# Sheet-3.net
KiCad netlist of a schematic drawn in Altium Designer
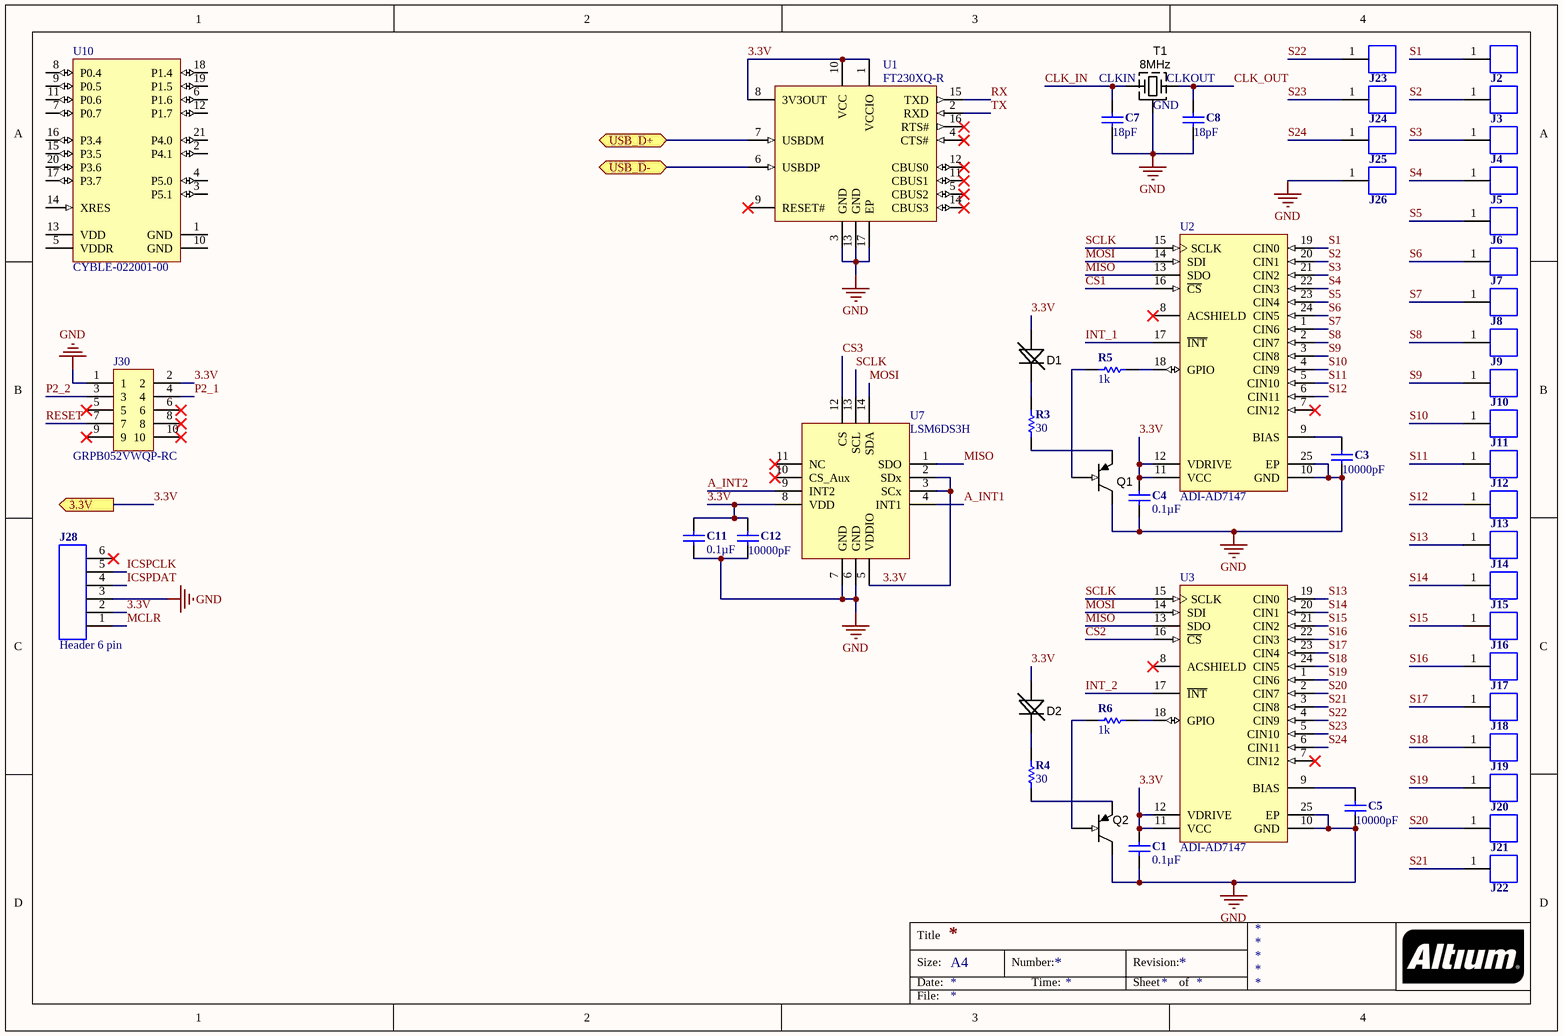
[diagram p0: Sheet-3.SchDoc]

(export (version "E")
  (design (tool "Eeschema 10.0.6"))
  (components
    (comp (ref "C1")
      (value "0.1µF")
      (footprint "CAP-0805(2012)-R")
      (description "___ OHM ___ mW 0805(2012) SMD")
      (fields
        (field (name "MANUFACTURER") "Yageo")
        (field (name "MANUFACTURER PART NUMBER") "CC0805KRX7R9BB104")
      )
      (libsource (lib "Glove") (part "C-0805(2012)"))
    )
    (comp (ref "C3")
      (value "10000pF")
      (footprint "CAP-0805(2012)-R")
      (description "___ OHM ___ mW 0805(2012) SMD")
      (fields
        (field (name "MANUFACTURER") "Yageo")
        (field (name "MANUFACTURER PART NUMBER") "CC0805KRX7R9BB103")
      )
      (libsource (lib "Glove") (part "C-0805(2012)"))
    )
    (comp (ref "C4")
      (value "0.1µF")
      (footprint "CAP-0805(2012)-R")
      (description "___ OHM ___ mW 0805(2012) SMD")
      (fields
        (field (name "MANUFACTURER") "Yageo")
        (field (name "MANUFACTURER PART NUMBER") "CC0805KRX7R9BB104")
      )
      (libsource (lib "Glove") (part "C-0805(2012)"))
    )
    (comp (ref "C5")
      (value "10000pF")
      (footprint "CAP-0805(2012)-R")
      (description "___ OHM ___ mW 0805(2012) SMD")
      (fields
        (field (name "MANUFACTURER") "Yageo")
        (field (name "MANUFACTURER PART NUMBER") "CC0805KRX7R9BB103")
      )
      (libsource (lib "Glove") (part "C-0805(2012)"))
    )
    (comp (ref "C7")
      (value "18pF")
      (footprint "CAP-0805(2012)-R")
      (description "___ OHM ___ mW 0805(2012) SMD")
      (fields
        (field (name "MANUFACTURER") "Yageo")
        (field (name "MANUFACTURER PART NUMBER") "CC0805JRNPO9BN180")
      )
      (libsource (lib "Glove") (part "C-0805(2012)"))
    )
    (comp (ref "C8")
      (value "18pF")
      (footprint "CAP-0805(2012)-R")
      (description "___ OHM ___ mW 0805(2012) SMD")
      (fields
        (field (name "MANUFACTURER") "Yageo")
        (field (name "MANUFACTURER PART NUMBER") "CC0805JRNPO9BN180")
      )
      (libsource (lib "Glove") (part "C-0805(2012)"))
    )
    (comp (ref "C11")
      (value "0.1µF")
      (footprint "CAP-0805(2012)-R")
      (description "___ OHM ___ mW 0805(2012) SMD")
      (fields
        (field (name "MANUFACTURER") "Yageo")
        (field (name "MANUFACTURER PART NUMBER") "CC0805KRX7R9BB104")
      )
      (libsource (lib "Glove") (part "C-0805(2012)"))
    )
    (comp (ref "C12")
      (value "10000pF")
      (footprint "CAP-0805(2012)-R")
      (description "___ OHM ___ mW 0805(2012) SMD")
      (fields
        (field (name "MANUFACTURER") "Yageo")
        (field (name "MANUFACTURER PART NUMBER") "CC0805KRX7R9BB103")
      )
      (libsource (lib "Glove") (part "C-0805(2012)"))
    )
    (comp (ref "D1")
      (value "YELLOW")
      (footprint "LED-0805-A")
      (description "LED, 0805 SMD, YELLOW")
      (fields
        (field (name "MANUFACTURER") "OSRAM Opto Semiconductors Inc.")
        (field (name "MANUFACTURER PART NUMBER") "LY R976-PS-36")
      )
      (libsource (lib "Glove") (part "LED_0805_YELLOW"))
    )
    (comp (ref "D2")
      (value "YELLOW")
      (footprint "LED-0805-A")
      (description "LED, 0805 SMD, YELLOW")
      (fields
        (field (name "MANUFACTURER") "OSRAM Opto Semiconductors Inc.")
        (field (name "MANUFACTURER PART NUMBER") "LY R976-PS-36")
      )
      (libsource (lib "Glove") (part "LED_0805_YELLOW"))
    )
    (comp (ref "J2")
      (value "Conductive Thread")
      (footprint "THREAD_HOLE")
      (description "Header, 1 pin, Conductive Thread")
      (libsource (lib "Glove") (part "CON-1_Pin_Thread"))
    )
    (comp (ref "J3")
      (value "Conductive Thread")
      (footprint "THREAD_HOLE")
      (description "Header, 1 pin, Conductive Thread")
      (libsource (lib "Glove") (part "CON-1_Pin_Thread"))
    )
    (comp (ref "J4")
      (value "Conductive Thread")
      (footprint "THREAD_HOLE")
      (description "Header, 1 pin, Conductive Thread")
      (libsource (lib "Glove") (part "CON-1_Pin_Thread"))
    )
    (comp (ref "J5")
      (value "Conductive Thread")
      (footprint "THREAD_HOLE")
      (description "Header, 1 pin, Conductive Thread")
      (libsource (lib "Glove") (part "CON-1_Pin_Thread"))
    )
    (comp (ref "J6")
      (value "Conductive Thread")
      (footprint "THREAD_HOLE")
      (description "Header, 1 pin, Conductive Thread")
      (libsource (lib "Glove") (part "CON-1_Pin_Thread"))
    )
    (comp (ref "J7")
      (value "Conductive Thread")
      (footprint "THREAD_HOLE")
      (description "Header, 1 pin, Conductive Thread")
      (libsource (lib "Glove") (part "CON-1_Pin_Thread"))
    )
    (comp (ref "J8")
      (value "Conductive Thread")
      (footprint "THREAD_HOLE")
      (description "Header, 1 pin, Conductive Thread")
      (libsource (lib "Glove") (part "CON-1_Pin_Thread"))
    )
    (comp (ref "J9")
      (value "Conductive Thread")
      (footprint "THREAD_HOLE")
      (description "Header, 1 pin, Conductive Thread")
      (libsource (lib "Glove") (part "CON-1_Pin_Thread"))
    )
    (comp (ref "J10")
      (value "Conductive Thread")
      (footprint "THREAD_HOLE")
      (description "Header, 1 pin, Conductive Thread")
      (libsource (lib "Glove") (part "CON-1_Pin_Thread"))
    )
    (comp (ref "J11")
      (value "Conductive Thread")
      (footprint "THREAD_HOLE")
      (description "Header, 1 pin, Conductive Thread")
      (libsource (lib "Glove") (part "CON-1_Pin_Thread"))
    )
    (comp (ref "J12")
      (value "Conductive Thread")
      (footprint "THREAD_HOLE")
      (description "Header, 1 pin, Conductive Thread")
      (libsource (lib "Glove") (part "CON-1_Pin_Thread"))
    )
    (comp (ref "J13")
      (value "Conductive Thread")
      (footprint "THREAD_HOLE")
      (description "Header, 1 pin, Conductive Thread")
      (libsource (lib "Glove") (part "CON-1_Pin_Thread"))
    )
    (comp (ref "J14")
      (value "Conductive Thread")
      (footprint "THREAD_HOLE")
      (description "Header, 1 pin, Conductive Thread")
      (libsource (lib "Glove") (part "CON-1_Pin_Thread"))
    )
    (comp (ref "J15")
      (value "Conductive Thread")
      (footprint "THREAD_HOLE")
      (description "Header, 1 pin, Conductive Thread")
      (libsource (lib "Glove") (part "CON-1_Pin_Thread"))
    )
    (comp (ref "J16")
      (value "Conductive Thread")
      (footprint "THREAD_HOLE")
      (description "Header, 1 pin, Conductive Thread")
      (libsource (lib "Glove") (part "CON-1_Pin_Thread"))
    )
    (comp (ref "J17")
      (value "Conductive Thread")
      (footprint "THREAD_HOLE")
      (description "Header, 1 pin, Conductive Thread")
      (libsource (lib "Glove") (part "CON-1_Pin_Thread"))
    )
    (comp (ref "J18")
      (value "Conductive Thread")
      (footprint "THREAD_HOLE")
      (description "Header, 1 pin, Conductive Thread")
      (libsource (lib "Glove") (part "CON-1_Pin_Thread"))
    )
    (comp (ref "J19")
      (value "Conductive Thread")
      (footprint "THREAD_HOLE")
      (description "Header, 1 pin, Conductive Thread")
      (libsource (lib "Glove") (part "CON-1_Pin_Thread"))
    )
    (comp (ref "J20")
      (value "Conductive Thread")
      (footprint "THREAD_HOLE")
      (description "Header, 1 pin, Conductive Thread")
      (libsource (lib "Glove") (part "CON-1_Pin_Thread"))
    )
    (comp (ref "J21")
      (value "Conductive Thread")
      (footprint "THREAD_HOLE")
      (description "Header, 1 pin, Conductive Thread")
      (libsource (lib "Glove") (part "CON-1_Pin_Thread"))
    )
    (comp (ref "J22")
      (value "Conductive Thread")
      (footprint "THREAD_HOLE")
      (description "Header, 1 pin, Conductive Thread")
      (libsource (lib "Glove") (part "CON-1_Pin_Thread"))
    )
    (comp (ref "J23")
      (value "Conductive Thread")
      (footprint "THREAD_HOLE")
      (description "Header, 1 pin, Conductive Thread")
      (libsource (lib "Glove") (part "CON-1_Pin_Thread"))
    )
    (comp (ref "J24")
      (value "Conductive Thread")
      (footprint "THREAD_HOLE")
      (description "Header, 1 pin, Conductive Thread")
      (libsource (lib "Glove") (part "CON-1_Pin_Thread"))
    )
    (comp (ref "J25")
      (value "Conductive Thread")
      (footprint "THREAD_HOLE")
      (description "Header, 1 pin, Conductive Thread")
      (libsource (lib "Glove") (part "CON-1_Pin_Thread"))
    )
    (comp (ref "J26")
      (value "Conductive Thread")
      (footprint "THREAD_HOLE")
      (description "Header, 1 pin, Conductive Thread")
      (libsource (lib "Glove") (part "CON-1_Pin_Thread"))
    )
    (comp (ref "J28")
      (value "Header 6 pin")
      (footprint "HEADER-6-100mil")
      (description "Header, 6 pin, .1 pitch")
      (fields
        (field (name "MANUFACTURER") "Amphenol FCI")
        (field (name "MANUFACTURER PART NUMBER") "68000-406HLF")
      )
      (libsource (lib "Glove") (part "CON-6Pin-100Mil"))
    )
    (comp (ref "J30")
      (value "GRPB052VWQP-RC")
      (footprint "GRPB052VWQP-RC")
      (description "CONN HEADER .050\" 10PS DL SMD AU")
      (fields (field (name "MANUFACTURER") "Sullins Connector Solutions"))
      (libsource (lib "UCSD Protolab") (part "GRPB052VWQP-RC"))
    )
    (comp (ref "Q1")
      (value "~")
      (footprint "SOT23-3")
      (description "Transistor PNP")
      (fields
        (field (name "MANUFACTURER") "Diodes Incorporated")
        (field (name "MANUFACTURER PART NUMBER") "FMMT591TA")
      )
      (libsource (lib "Glove") (part "FMMT591CT-ND"))
    )
    (comp (ref "Q2")
      (value "~")
      (footprint "SOT23-3")
      (description "Transistor PNP")
      (fields
        (field (name "MANUFACTURER") "Diodes Incorporated")
        (field (name "MANUFACTURER PART NUMBER") "FMMT591TA")
      )
      (libsource (lib "Glove") (part "FMMT591CT-ND"))
    )
    (comp (ref "R3")
      (value "30")
      (footprint "R-0805(2012)-R")
      (description "___ OHM ___ mW 0805(2012) SMD")
      (fields
        (field (name "MANUFACTURER") "Yageo")
        (field (name "MANUFACTURER PART NUMBER") "RC0805JR-0730RL")
      )
      (libsource (lib "Glove") (part "R-0805(2012)"))
    )
    (comp (ref "R4")
      (value "30")
      (footprint "R-0805(2012)-R")
      (description "___ OHM ___ mW 0805(2012) SMD")
      (fields
        (field (name "MANUFACTURER") "Yageo")
        (field (name "MANUFACTURER PART NUMBER") "RC0805JR-0730RL")
      )
      (libsource (lib "Glove") (part "R-0805(2012)"))
    )
    (comp (ref "R5")
      (value "1k")
      (footprint "R-0805(2012)-R")
      (description "___ OHM ___ mW 0805(2012) SMD")
      (fields
        (field (name "MANUFACTURER") "Yageo")
        (field (name "MANUFACTURER PART NUMBER") "RC0805JR-071KL")
      )
      (libsource (lib "Glove") (part "R-0805(2012)"))
    )
    (comp (ref "R6")
      (value "1k")
      (footprint "R-0805(2012)-R")
      (description "___ OHM ___ mW 0805(2012) SMD")
      (fields
        (field (name "MANUFACTURER") "Yageo")
        (field (name "MANUFACTURER PART NUMBER") "RC0805JR-071KL")
      )
      (libsource (lib "Glove") (part "R-0805(2012)"))
    )
    (comp (ref "T1")
      (value "8MHz")
      (footprint "CRYSTAL-8MHZ")
      (description "Oscillator Crystal 8MHz 10ppm")
      (fields
        (field (name "MANUFACTURER") "Abracon LLC")
        (field (name "MANUFACTURER PART NUMBER") "ABMM2-8.000MHZ-E2-T")
      )
      (libsource (lib "Glove") (part "CRYSTAL_8MHz"))
    )
    (comp (ref "U1")
      (value "FT230XQ-R")
      (footprint "QFN-16")
      (fields (field (name "MANUFACTURER") "FTDI, Future Technology Devices International Ltd"))
      (libsource (lib "Glove") (part "FT230XQ-R"))
    )
    (comp (ref "U2")
      (value "ADI-AD7147")
      (footprint "LFCSP_WQ")
      (fields
        (field (name "MANUFACTURER") "Analog Devices Inc.")
        (field (name "MANUFACTURER PART NUMBER") "AD7147PACPZ-500R7")
      )
      (libsource (lib "Glove") (part "ADI-AD7147"))
    )
    (comp (ref "U3")
      (value "ADI-AD7147")
      (footprint "LFCSP_WQ")
      (fields
        (field (name "MANUFACTURER") "Analog Devices Inc.")
        (field (name "MANUFACTURER PART NUMBER") "AD7147PACPZ-500R7")
      )
      (libsource (lib "Glove") (part "ADI-AD7147"))
    )
    (comp (ref "U7")
      (value "LSM6DS3H")
      (footprint "LGA-14")
      (description "3D accelerometer and 3D gyroscope")
      (fields
        (field (name "MANUFACTURER") "STMicroelectronics")
        (field (name "MANUFACTURER PART NUMBER") "LSM6DS3HTR")
      )
      (libsource (lib "Glove") (part "LSM6DS3H"))
    )
    (comp (ref "U10")
      (value "CYBLE-022001-00")
      (footprint "CYP-SP21_V")
      (description "RF Transceiver Module, 128 kB Flash, -40 to 85 degC, 21-Pin Module, RoHS")
      (fields (field (name "MANUFACTURER") "CypressSemiconductorCorp"))
      (libsource (lib "Altium Content Vault") (part "CYP-CYBLE-022001-00-21"))
    )
  )
  (nets
    (net (code "1") (name "/3.3V") (class "Default")
      (node (ref "C1") (pin "1") (pinfunction "1_1") (pintype "passive"))
      (node (ref "C11") (pin "2") (pinfunction "2_2") (pintype "passive"))
      (node (ref "C12") (pin "2") (pinfunction "2_2") (pintype "passive"))
      (node (ref "C4") (pin "1") (pinfunction "1_1") (pintype "passive"))
      (node (ref "D1") (pin "A") (pinfunction "A_A") (pintype "passive"))
      (node (ref "D2") (pin "A") (pinfunction "A_A") (pintype "passive"))
      (node (ref "J28") (pin "2") (pinfunction "2_2") (pintype "passive"))
      (node (ref "J30") (pin "2") (pinfunction "2_2") (pintype "passive"))
      (node (ref "U1") (pin "1") (pinfunction "VCCIO_1") (pintype "power_in"))
      (node (ref "U1") (pin "10") (pinfunction "VCC_10") (pintype "power_in"))
      (node (ref "U1") (pin "8") (pinfunction "3V3OUT_8") (pintype "power_in"))
      (node (ref "U2") (pin "11") (pinfunction "VCC_11") (pintype "power_in"))
      (node (ref "U2") (pin "12") (pinfunction "VDRIVE_12") (pintype "power_in"))
      (node (ref "U3") (pin "11") (pinfunction "VCC_11") (pintype "power_in"))
      (node (ref "U3") (pin "12") (pinfunction "VDRIVE_12") (pintype "power_in"))
      (node (ref "U7") (pin "2") (pinfunction "SDx_2") (pintype "passive"))
      (node (ref "U7") (pin "3") (pinfunction "SCx_3") (pintype "passive"))
      (node (ref "U7") (pin "5") (pinfunction "VDDIO_5") (pintype "passive"))
      (node (ref "U7") (pin "8") (pinfunction "VDD_8") (pintype "passive"))
    )
    (net (code "2") (name "/A_INT1") (class "Default")
      (node (ref "U7") (pin "4") (pinfunction "INT1_4") (pintype "passive"))
    )
    (net (code "3") (name "/A_INT2") (class "Default")
      (node (ref "U7") (pin "9") (pinfunction "INT2_9") (pintype "passive"))
    )
    (net (code "4") (name "/CLK_IN") (class "Default")
      (node (ref "C7") (pin "1") (pinfunction "1_1") (pintype "passive"))
      (node (ref "T1") (pin "1") (pinfunction "CLKIN_1") (pintype "passive"))
    )
    (net (code "5") (name "/CLK_OUT") (class "Default")
      (node (ref "C8") (pin "1") (pinfunction "1_1") (pintype "passive"))
      (node (ref "T1") (pin "3") (pinfunction "X_3") (pintype "passive"))
    )
    (net (code "6") (name "/CS1") (class "Default")
      (node (ref "U2") (pin "16") (pinfunction "~{CS}_16") (pintype "input"))
    )
    (net (code "7") (name "/CS2") (class "Default")
      (node (ref "U3") (pin "16") (pinfunction "~{CS}_16") (pintype "input"))
    )
    (net (code "8") (name "/CS3") (class "Default")
      (node (ref "U7") (pin "12") (pinfunction "CS_12") (pintype "passive"))
    )
    (net (code "9") (name "/ICSPCLK") (class "Default")
      (node (ref "J28") (pin "5") (pinfunction "5_5") (pintype "passive"))
    )
    (net (code "10") (name "/ICSPDAT") (class "Default")
      (node (ref "J28") (pin "4") (pinfunction "4_4") (pintype "passive"))
    )
    (net (code "11") (name "/INT_1") (class "Default")
      (node (ref "U2") (pin "17") (pinfunction "~{INT}_17") (pintype "open_collector"))
    )
    (net (code "12") (name "/INT_2") (class "Default")
      (node (ref "U3") (pin "17") (pinfunction "~{INT}_17") (pintype "open_collector"))
    )
    (net (code "13") (name "/MCLR") (class "Default")
      (node (ref "J28") (pin "1") (pinfunction "1_1") (pintype "passive"))
    )
    (net (code "14") (name "/MISO") (class "Default")
      (node (ref "U2") (pin "13") (pinfunction "SDO_13") (pintype "tri_state"))
      (node (ref "U3") (pin "13") (pinfunction "SDO_13") (pintype "tri_state"))
      (node (ref "U7") (pin "1") (pinfunction "SDO_1") (pintype "passive"))
    )
    (net (code "15") (name "/MOSI") (class "Default")
      (node (ref "U2") (pin "14") (pinfunction "SDI_14") (pintype "input"))
      (node (ref "U3") (pin "14") (pinfunction "SDI_14") (pintype "input"))
      (node (ref "U7") (pin "14") (pinfunction "SDA_14") (pintype "passive"))
    )
    (net (code "16") (name "/P2_1") (class "Default")
      (node (ref "J30") (pin "4") (pinfunction "4_4") (pintype "passive"))
    )
    (net (code "17") (name "/P2_2") (class "Default")
      (node (ref "J30") (pin "3") (pinfunction "3_3") (pintype "passive"))
    )
    (net (code "18") (name "/RESET") (class "Default")
      (node (ref "J30") (pin "7") (pinfunction "7_7") (pintype "passive"))
    )
    (net (code "19") (name "/RX") (class "Default")
      (node (ref "U1") (pin "15") (pinfunction "TXD_15") (pintype "output"))
    )
    (net (code "20") (name "/S1") (class "Default")
      (node (ref "J2") (pin "1") (pinfunction "1_1") (pintype "passive"))
      (node (ref "U2") (pin "19") (pinfunction "CIN0_19") (pintype "input"))
    )
    (net (code "21") (name "/S2") (class "Default")
      (node (ref "J3") (pin "1") (pinfunction "1_1") (pintype "passive"))
      (node (ref "U2") (pin "20") (pinfunction "CIN1_20") (pintype "input"))
    )
    (net (code "22") (name "/S3") (class "Default")
      (node (ref "J4") (pin "1") (pinfunction "1_1") (pintype "passive"))
      (node (ref "U2") (pin "21") (pinfunction "CIN2_21") (pintype "input"))
    )
    (net (code "23") (name "/S4") (class "Default")
      (node (ref "J5") (pin "1") (pinfunction "1_1") (pintype "passive"))
      (node (ref "U2") (pin "22") (pinfunction "CIN3_22") (pintype "input"))
    )
    (net (code "24") (name "/S5") (class "Default")
      (node (ref "J6") (pin "1") (pinfunction "1_1") (pintype "passive"))
      (node (ref "U2") (pin "23") (pinfunction "CIN4_23") (pintype "input"))
    )
    (net (code "25") (name "/S6") (class "Default")
      (node (ref "J7") (pin "1") (pinfunction "1_1") (pintype "passive"))
      (node (ref "U2") (pin "24") (pinfunction "CIN5_24") (pintype "input"))
    )
    (net (code "26") (name "/S7") (class "Default")
      (node (ref "J8") (pin "1") (pinfunction "1_1") (pintype "passive"))
      (node (ref "U2") (pin "1") (pinfunction "CIN6_1") (pintype "input"))
    )
    (net (code "27") (name "/S8") (class "Default")
      (node (ref "J9") (pin "1") (pinfunction "1_1") (pintype "passive"))
      (node (ref "U2") (pin "2") (pinfunction "CIN7_2") (pintype "input"))
    )
    (net (code "28") (name "/S9") (class "Default")
      (node (ref "J10") (pin "1") (pinfunction "1_1") (pintype "passive"))
      (node (ref "U2") (pin "3") (pinfunction "CIN8_3") (pintype "input"))
    )
    (net (code "29") (name "/S10") (class "Default")
      (node (ref "J11") (pin "1") (pinfunction "1_1") (pintype "passive"))
      (node (ref "U2") (pin "4") (pinfunction "CIN9_4") (pintype "input"))
    )
    (net (code "30") (name "/S11") (class "Default")
      (node (ref "J12") (pin "1") (pinfunction "1_1") (pintype "passive"))
      (node (ref "U2") (pin "5") (pinfunction "CIN10_5") (pintype "input"))
    )
    (net (code "31") (name "/S12") (class "Default")
      (node (ref "J13") (pin "1") (pinfunction "1_1") (pintype "passive"))
      (node (ref "U2") (pin "6") (pinfunction "CIN11_6") (pintype "input"))
    )
    (net (code "32") (name "/S13") (class "Default")
      (node (ref "J14") (pin "1") (pinfunction "1_1") (pintype "passive"))
      (node (ref "U3") (pin "19") (pinfunction "CIN0_19") (pintype "input"))
    )
    (net (code "33") (name "/S14") (class "Default")
      (node (ref "J15") (pin "1") (pinfunction "1_1") (pintype "passive"))
      (node (ref "U3") (pin "20") (pinfunction "CIN1_20") (pintype "input"))
    )
    (net (code "34") (name "/S15") (class "Default")
      (node (ref "J16") (pin "1") (pinfunction "1_1") (pintype "passive"))
      (node (ref "U3") (pin "21") (pinfunction "CIN2_21") (pintype "input"))
    )
    (net (code "35") (name "/S16") (class "Default")
      (node (ref "J17") (pin "1") (pinfunction "1_1") (pintype "passive"))
      (node (ref "U3") (pin "22") (pinfunction "CIN3_22") (pintype "input"))
    )
    (net (code "36") (name "/S17") (class "Default")
      (node (ref "J18") (pin "1") (pinfunction "1_1") (pintype "passive"))
      (node (ref "U3") (pin "23") (pinfunction "CIN4_23") (pintype "input"))
    )
    (net (code "37") (name "/S18") (class "Default")
      (node (ref "J19") (pin "1") (pinfunction "1_1") (pintype "passive"))
      (node (ref "U3") (pin "24") (pinfunction "CIN5_24") (pintype "input"))
    )
    (net (code "38") (name "/S19") (class "Default")
      (node (ref "J20") (pin "1") (pinfunction "1_1") (pintype "passive"))
      (node (ref "U3") (pin "1") (pinfunction "CIN6_1") (pintype "input"))
    )
    (net (code "39") (name "/S20") (class "Default")
      (node (ref "J21") (pin "1") (pinfunction "1_1") (pintype "passive"))
      (node (ref "U3") (pin "2") (pinfunction "CIN7_2") (pintype "input"))
    )
    (net (code "40") (name "/S21") (class "Default")
      (node (ref "J22") (pin "1") (pinfunction "1_1") (pintype "passive"))
      (node (ref "U3") (pin "3") (pinfunction "CIN8_3") (pintype "input"))
    )
    (net (code "41") (name "/S22") (class "Default")
      (node (ref "J23") (pin "1") (pinfunction "1_1") (pintype "passive"))
      (node (ref "U3") (pin "4") (pinfunction "CIN9_4") (pintype "input"))
    )
    (net (code "42") (name "/S23") (class "Default")
      (node (ref "J24") (pin "1") (pinfunction "1_1") (pintype "passive"))
      (node (ref "U3") (pin "5") (pinfunction "CIN10_5") (pintype "input"))
    )
    (net (code "43") (name "/S24") (class "Default")
      (node (ref "J25") (pin "1") (pinfunction "1_1") (pintype "passive"))
      (node (ref "U3") (pin "6") (pinfunction "CIN11_6") (pintype "input"))
    )
    (net (code "44") (name "/SCLK") (class "Default")
      (node (ref "U2") (pin "15") (pinfunction "SCLK_15") (pintype "input"))
      (node (ref "U3") (pin "15") (pinfunction "SCLK_15") (pintype "input"))
      (node (ref "U7") (pin "13") (pinfunction "SCL_13") (pintype "passive"))
    )
    (net (code "45") (name "/TX") (class "Default")
      (node (ref "U1") (pin "2") (pinfunction "RXD_2") (pintype "input"))
    )
    (net (code "46") (name "/USB_D+") (class "Default")
      (node (ref "U1") (pin "7") (pinfunction "USBDM_7") (pintype "input"))
    )
    (net (code "47") (name "/USB_D-") (class "Default")
      (node (ref "U1") (pin "6") (pinfunction "USBDP_6") (pintype "input"))
    )
    (net (code "48") (name "GND") (class "Default")
      (node (ref "C1") (pin "2") (pinfunction "2_2") (pintype "passive"))
      (node (ref "C11") (pin "1") (pinfunction "1_1") (pintype "passive"))
      (node (ref "C12") (pin "1") (pinfunction "1_1") (pintype "passive"))
      (node (ref "C3") (pin "2") (pinfunction "2_2") (pintype "passive"))
      (node (ref "C4") (pin "2") (pinfunction "2_2") (pintype "passive"))
      (node (ref "C5") (pin "2") (pinfunction "2_2") (pintype "passive"))
      (node (ref "C7") (pin "2") (pinfunction "2_2") (pintype "passive"))
      (node (ref "C8") (pin "2") (pinfunction "2_2") (pintype "passive"))
      (node (ref "J26") (pin "1") (pinfunction "1_1") (pintype "passive"))
      (node (ref "J28") (pin "3") (pinfunction "3_3") (pintype "passive"))
      (node (ref "J30") (pin "1") (pinfunction "1_1") (pintype "passive"))
      (node (ref "Q1") (pin "2") (pinfunction "C_2") (pintype "passive"))
      (node (ref "Q2") (pin "2") (pinfunction "C_2") (pintype "passive"))
      (node (ref "T1") (pin "2") (pinfunction "GND_2") (pintype "passive"))
      (node (ref "U1") (pin "13") (pinfunction "GND_13") (pintype "power_in"))
      (node (ref "U1") (pin "17") (pinfunction "EP_17") (pintype "power_in"))
      (node (ref "U1") (pin "3") (pinfunction "GND_3") (pintype "power_in"))
      (node (ref "U2") (pin "10") (pinfunction "GND_10") (pintype "power_in"))
      (node (ref "U2") (pin "25") (pinfunction "EP_25") (pintype "power_in"))
      (node (ref "U3") (pin "10") (pinfunction "GND_10") (pintype "power_in"))
      (node (ref "U3") (pin "25") (pinfunction "EP_25") (pintype "power_in"))
      (node (ref "U7") (pin "6") (pinfunction "GND_6") (pintype "passive"))
      (node (ref "U7") (pin "7") (pinfunction "GND_7") (pintype "passive"))
    )
    (net (code "49") (name "Net-(D1-PadK)") (class "Default")
      (node (ref "D1") (pin "K") (pinfunction "K_K") (pintype "passive"))
      (node (ref "R3") (pin "2") (pinfunction "2_2") (pintype "passive"))
    )
    (net (code "50") (name "Net-(D2-PadK)") (class "Default")
      (node (ref "D2") (pin "K") (pinfunction "K_K") (pintype "passive"))
      (node (ref "R4") (pin "2") (pinfunction "2_2") (pintype "passive"))
    )
    (net (code "51") (name "Net-(Q1-B)") (class "Default")
      (node (ref "Q1") (pin "1") (pinfunction "B_1") (pintype "input"))
      (node (ref "R5") (pin "1") (pinfunction "1_1") (pintype "passive"))
    )
    (net (code "52") (name "Net-(Q1-E)") (class "Default")
      (node (ref "Q1") (pin "3") (pinfunction "E_3") (pintype "passive"))
      (node (ref "R3") (pin "1") (pinfunction "1_1") (pintype "passive"))
    )
    (net (code "53") (name "Net-(Q2-B)") (class "Default")
      (node (ref "Q2") (pin "1") (pinfunction "B_1") (pintype "input"))
      (node (ref "R6") (pin "2") (pinfunction "2_2") (pintype "passive"))
    )
    (net (code "54") (name "Net-(Q2-E)") (class "Default")
      (node (ref "Q2") (pin "3") (pinfunction "E_3") (pintype "passive"))
      (node (ref "R4") (pin "1") (pinfunction "1_1") (pintype "passive"))
    )
    (net (code "55") (name "Net-(U2-BIAS)") (class "Default")
      (node (ref "C3") (pin "1") (pinfunction "1_1") (pintype "passive"))
      (node (ref "U2") (pin "9") (pinfunction "BIAS_9") (pintype "passive"))
    )
    (net (code "56") (name "Net-(U2-GPIO)") (class "Default")
      (node (ref "R5") (pin "2") (pinfunction "2_2") (pintype "passive"))
      (node (ref "U2") (pin "18") (pinfunction "GPIO_18") (pintype "bidirectional"))
    )
    (net (code "57") (name "Net-(U3-BIAS)") (class "Default")
      (node (ref "C5") (pin "1") (pinfunction "1_1") (pintype "passive"))
      (node (ref "U3") (pin "9") (pinfunction "BIAS_9") (pintype "passive"))
    )
    (net (code "58") (name "Net-(U3-GPIO)") (class "Default")
      (node (ref "R6") (pin "1") (pinfunction "1_1") (pintype "passive"))
      (node (ref "U3") (pin "18") (pinfunction "GPIO_18") (pintype "bidirectional"))
    )
    (net (code "59") (name "unconnected-(J28-Pad6)") (class "Default")
      (node (ref "J28") (pin "6") (pinfunction "6_6") (pintype "passive+no_connect"))
    )
    (net (code "60") (name "unconnected-(J30-Pad5)") (class "Default")
      (node (ref "J30") (pin "5") (pinfunction "5_5") (pintype "passive+no_connect"))
    )
    (net (code "61") (name "unconnected-(J30-Pad6)") (class "Default")
      (node (ref "J30") (pin "6") (pinfunction "6_6") (pintype "passive+no_connect"))
    )
    (net (code "62") (name "unconnected-(J30-Pad8)") (class "Default")
      (node (ref "J30") (pin "8") (pinfunction "8_8") (pintype "passive+no_connect"))
    )
    (net (code "63") (name "unconnected-(J30-Pad9)") (class "Default")
      (node (ref "J30") (pin "9") (pinfunction "9_9") (pintype "passive+no_connect"))
    )
    (net (code "64") (name "unconnected-(J30-Pad10)") (class "Default")
      (node (ref "J30") (pin "10") (pinfunction "10_10") (pintype "passive+no_connect"))
    )
    (net (code "65") (name "unconnected-(U1-CBUS0-Pad12)") (class "Default")
      (node (ref "U1") (pin "12") (pinfunction "CBUS0_12") (pintype "bidirectional+no_connect"))
    )
    (net (code "66") (name "unconnected-(U1-CBUS1-Pad11)") (class "Default")
      (node (ref "U1") (pin "11") (pinfunction "CBUS1_11") (pintype "bidirectional+no_connect"))
    )
    (net (code "67") (name "unconnected-(U1-CBUS2-Pad5)") (class "Default")
      (node (ref "U1") (pin "5") (pinfunction "CBUS2_5") (pintype "bidirectional+no_connect"))
    )
    (net (code "68") (name "unconnected-(U1-CBUS3-Pad14)") (class "Default")
      (node (ref "U1") (pin "14") (pinfunction "CBUS3_14") (pintype "bidirectional+no_connect"))
    )
    (net (code "69") (name "unconnected-(U1-CTS#-Pad4)") (class "Default")
      (node (ref "U1") (pin "4") (pinfunction "CTS#_4") (pintype "input+no_connect"))
    )
    (net (code "70") (name "unconnected-(U1-RESET#-Pad9)") (class "Default")
      (node (ref "U1") (pin "9") (pinfunction "RESET#_9") (pintype "passive+no_connect"))
    )
    (net (code "71") (name "unconnected-(U1-RTS#-Pad16)") (class "Default")
      (node (ref "U1") (pin "16") (pinfunction "RTS#_16") (pintype "output+no_connect"))
    )
    (net (code "72") (name "unconnected-(U2-ACSHIELD-Pad8)") (class "Default")
      (node (ref "U2") (pin "8") (pinfunction "ACSHIELD_8") (pintype "passive+no_connect"))
    )
    (net (code "73") (name "unconnected-(U2-CIN12-Pad7)") (class "Default")
      (node (ref "U2") (pin "7") (pinfunction "CIN12_7") (pintype "input+no_connect"))
    )
    (net (code "74") (name "unconnected-(U3-ACSHIELD-Pad8)") (class "Default")
      (node (ref "U3") (pin "8") (pinfunction "ACSHIELD_8") (pintype "passive+no_connect"))
    )
    (net (code "75") (name "unconnected-(U3-CIN12-Pad7)") (class "Default")
      (node (ref "U3") (pin "7") (pinfunction "CIN12_7") (pintype "input+no_connect"))
    )
    (net (code "76") (name "unconnected-(U7-CS_Aux-Pad10)") (class "Default")
      (node (ref "U7") (pin "10") (pinfunction "CS_Aux_10") (pintype "passive+no_connect"))
    )
    (net (code "77") (name "unconnected-(U7-NC-Pad11)") (class "Default")
      (node (ref "U7") (pin "11") (pinfunction "NC_11") (pintype "passive+no_connect"))
    )
    (net (code "78") (name "unconnected-(U10-GND-Pad1)") (class "Default")
      (node (ref "U10") (pin "1") (pinfunction "GND_1") (pintype "power_in"))
    )
    (net (code "79") (name "unconnected-(U10-GND-Pad10)") (class "Default")
      (node (ref "U10") (pin "10") (pinfunction "GND_10") (pintype "power_in"))
    )
    (net (code "80") (name "unconnected-(U10-P0.4-Pad8)") (class "Default")
      (node (ref "U10") (pin "8") (pinfunction "P0.4_8") (pintype "bidirectional"))
    )
    (net (code "81") (name "unconnected-(U10-P0.5-Pad9)") (class "Default")
      (node (ref "U10") (pin "9") (pinfunction "P0.5_9") (pintype "bidirectional"))
    )
    (net (code "82") (name "unconnected-(U10-P0.6-Pad11)") (class "Default")
      (node (ref "U10") (pin "11") (pinfunction "P0.6_11") (pintype "bidirectional"))
    )
    (net (code "83") (name "unconnected-(U10-P0.7-Pad7)") (class "Default")
      (node (ref "U10") (pin "7") (pinfunction "P0.7_7") (pintype "bidirectional"))
    )
    (net (code "84") (name "unconnected-(U10-P1.4-Pad18)") (class "Default")
      (node (ref "U10") (pin "18") (pinfunction "P1.4_18") (pintype "bidirectional"))
    )
    (net (code "85") (name "unconnected-(U10-P1.5-Pad19)") (class "Default")
      (node (ref "U10") (pin "19") (pinfunction "P1.5_19") (pintype "bidirectional"))
    )
    (net (code "86") (name "unconnected-(U10-P1.6-Pad6)") (class "Default")
      (node (ref "U10") (pin "6") (pinfunction "P1.6_6") (pintype "bidirectional"))
    )
    (net (code "87") (name "unconnected-(U10-P1.7-Pad12)") (class "Default")
      (node (ref "U10") (pin "12") (pinfunction "P1.7_12") (pintype "bidirectional"))
    )
    (net (code "88") (name "unconnected-(U10-P3.4-Pad16)") (class "Default")
      (node (ref "U10") (pin "16") (pinfunction "P3.4_16") (pintype "bidirectional"))
    )
    (net (code "89") (name "unconnected-(U10-P3.5-Pad15)") (class "Default")
      (node (ref "U10") (pin "15") (pinfunction "P3.5_15") (pintype "bidirectional"))
    )
    (net (code "90") (name "unconnected-(U10-P3.6-Pad20)") (class "Default")
      (node (ref "U10") (pin "20") (pinfunction "P3.6_20") (pintype "bidirectional"))
    )
    (net (code "91") (name "unconnected-(U10-P3.7-Pad17)") (class "Default")
      (node (ref "U10") (pin "17") (pinfunction "P3.7_17") (pintype "bidirectional"))
    )
    (net (code "92") (name "unconnected-(U10-P4.0-Pad21)") (class "Default")
      (node (ref "U10") (pin "21") (pinfunction "P4.0_21") (pintype "bidirectional"))
    )
    (net (code "93") (name "unconnected-(U10-P4.1-Pad2)") (class "Default")
      (node (ref "U10") (pin "2") (pinfunction "P4.1_2") (pintype "bidirectional"))
    )
    (net (code "94") (name "unconnected-(U10-P5.0-Pad4)") (class "Default")
      (node (ref "U10") (pin "4") (pinfunction "P5.0_4") (pintype "bidirectional"))
    )
    (net (code "95") (name "unconnected-(U10-P5.1-Pad3)") (class "Default")
      (node (ref "U10") (pin "3") (pinfunction "P5.1_3") (pintype "bidirectional"))
    )
    (net (code "96") (name "unconnected-(U10-VDD-Pad13)") (class "Default")
      (node (ref "U10") (pin "13") (pinfunction "VDD_13") (pintype "power_in"))
    )
    (net (code "97") (name "unconnected-(U10-VDDR-Pad5)") (class "Default")
      (node (ref "U10") (pin "5") (pinfunction "VDDR_5") (pintype "power_in"))
    )
    (net (code "98") (name "unconnected-(U10-XRES-Pad14)") (class "Default")
      (node (ref "U10") (pin "14") (pinfunction "XRES_14") (pintype "input"))
    )
  )
)
